# schematic.net
KiCad netlist of a schematic drawn in EAGLE
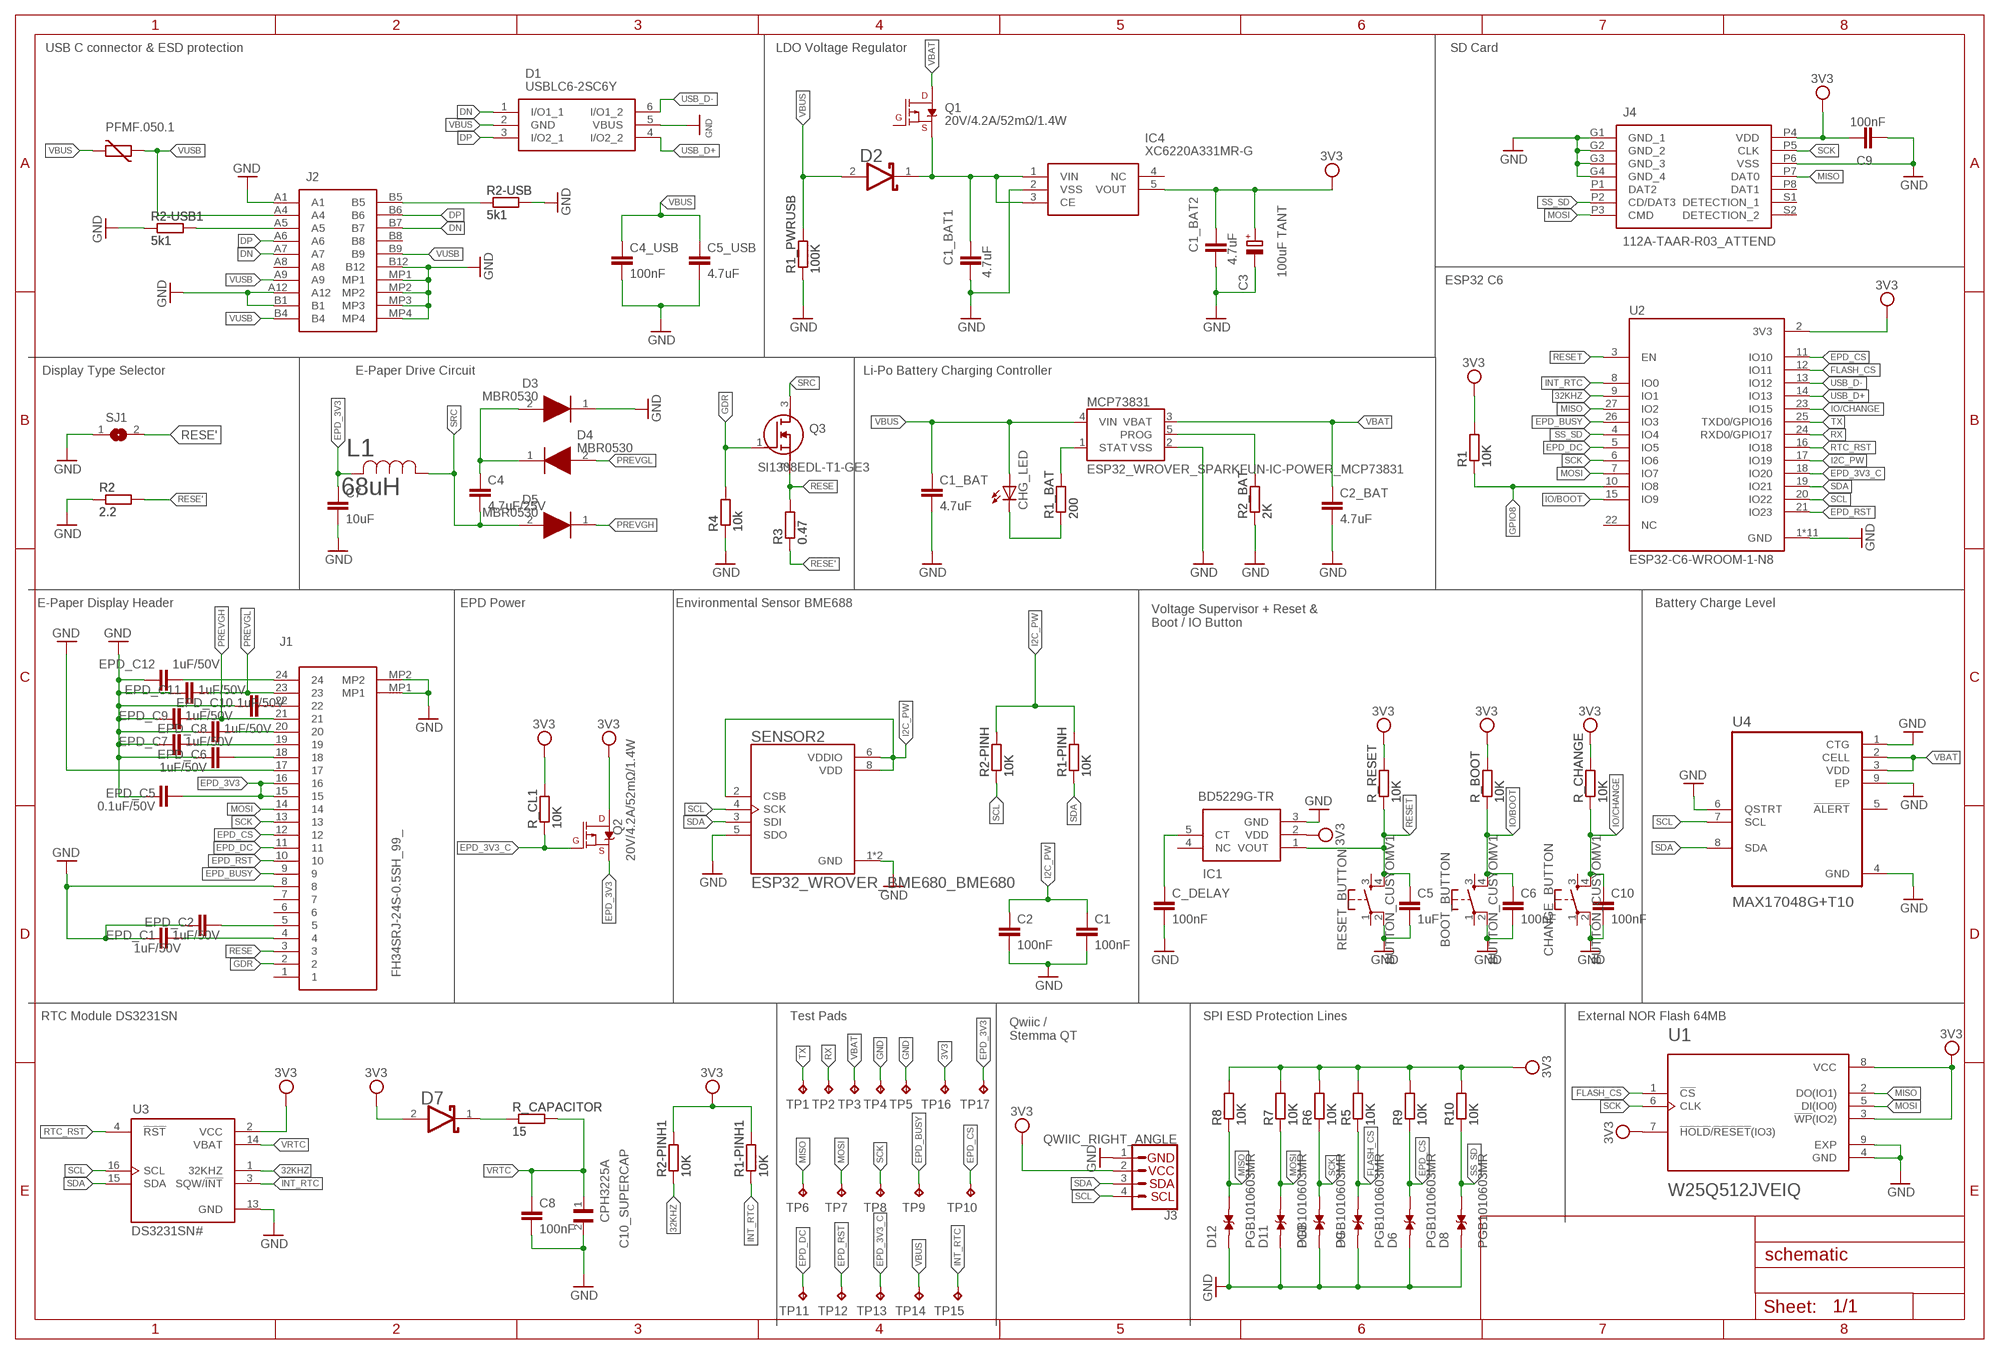
[diagram p0: schematic, sheet 1]

(export (version "E")
  (design (tool "Eeschema 10.0.6"))
  (components
    (comp (ref "BOOT_BUTTON")
      (value "BUTTON_CUSYOMV1")
      (footprint "eagle-import:MYBUTTON")
      (libsource (lib "eagle-import") (part "BUTTON_CUSYOMV1"))
    )
    (comp (ref "C1")
      (value "100nF")
      (footprint "eagle-import:EAGLE-LTSPICE_C0402")
      (libsource (lib "eagle-import") (part "ESP32_WROVER_EAGLE-LTSPICE_CC0402"))
    )
    (comp (ref "C1_BAT")
      (value "4.7uF")
      (footprint "eagle-import:EAGLE-LTSPICE_C0402")
      (libsource (lib "eagle-import") (part "ESP32_WROVER_EAGLE-LTSPICE_CC0402"))
    )
    (comp (ref "C1_BAT1")
      (value "4.7uF")
      (footprint "eagle-import:ESP32_WROVER_EAGLE-LTSPICE_C0402")
      (libsource (lib "eagle-import") (part "DeskAssistant v19 v1_vf.dFvje_iDQXiLOtX_eNBvag_EAGLE-LTSPICE_CC0402"))
    )
    (comp (ref "C1_BAT2")
      (value "4.7uF")
      (footprint "eagle-import:ESP32_WROVER_EAGLE-LTSPICE_C0402")
      (libsource (lib "eagle-import") (part "DeskAssistant v19 v1_vf.dFvje_iDQXiLOtX_eNBvag_EAGLE-LTSPICE_CC0402"))
    )
    (comp (ref "C2")
      (value "100nF")
      (footprint "eagle-import:EAGLE-LTSPICE_C0402")
      (libsource (lib "eagle-import") (part "ESP32_WROVER_EAGLE-LTSPICE_CC0402"))
    )
    (comp (ref "C2_BAT")
      (value "4.7uF")
      (footprint "eagle-import:EAGLE-LTSPICE_C0402")
      (libsource (lib "eagle-import") (part "ESP32_WROVER_EAGLE-LTSPICE_CC0402"))
    )
    (comp (ref "C3")
      (value "100uF TANT")
      (footprint "eagle-import:RCL_CT3528")
      (libsource (lib "eagle-import") (part "RCL_CPOL-EUCT3528"))
    )
    (comp (ref "C4")
      (value "4.7uF/25V")
      (footprint "eagle-import:EAGLE-LTSPICE_C0402")
      (libsource (lib "eagle-import") (part "ESP32_WROVER_EAGLE-LTSPICE_CC0402"))
    )
    (comp (ref "C4_USB")
      (value "100nF")
      (footprint "eagle-import:EAGLE-LTSPICE_C0402")
      (libsource (lib "eagle-import") (part "EAGLE-LTSPICE_CC0402"))
    )
    (comp (ref "C5")
      (value "1uF")
      (footprint "eagle-import:EAGLE-LTSPICE_C0402")
      (libsource (lib "eagle-import") (part "ESP32_WROVER_EAGLE-LTSPICE_CC0402"))
    )
    (comp (ref "C5_USB")
      (value "4.7uF")
      (footprint "eagle-import:EAGLE-LTSPICE_C0402")
      (libsource (lib "eagle-import") (part "EAGLE-LTSPICE_CC0402"))
    )
    (comp (ref "C6")
      (value "100nF")
      (footprint "eagle-import:EAGLE-LTSPICE_C0402")
      (libsource (lib "eagle-import") (part "ESP32_WROVER_EAGLE-LTSPICE_CC0402"))
    )
    (comp (ref "C7")
      (value "10uF")
      (footprint "eagle-import:EAGLE-LTSPICE_C0402")
      (libsource (lib "eagle-import") (part "ESP32_WROVER_EAGLE-LTSPICE_CC0402"))
    )
    (comp (ref "C8")
      (value "100nF")
      (footprint "eagle-import:EAGLE-LTSPICE_C0402")
      (libsource (lib "eagle-import") (part "ESP32_WROVER_EAGLE-LTSPICE_CC0402"))
    )
    (comp (ref "C9")
      (value "100nF")
      (footprint "eagle-import:ESP32_WROVER_EAGLE-LTSPICE_C0402")
      (libsource (lib "eagle-import") (part "DeskAssistant v19 v1_vf.dFvje_iDQXiLOtX_eNBvag_EAGLE-LTSPICE_CC0402"))
    )
    (comp (ref "C10")
      (value "100nF")
      (footprint "eagle-import:EAGLE-LTSPICE_C0402")
      (libsource (lib "eagle-import") (part "ESP32_WROVER_EAGLE-LTSPICE_CC0402"))
    )
    (comp (ref "C10_SUPERCAP")
      (value "CPH3225A")
      (footprint "eagle-import:CAPCP3225X100N")
      (fields (field (name "MF") "Seiko Instruments"))
      (libsource (lib "eagle-import") (part "CPH3225A"))
    )
    (comp (ref "CHANGE_BUTTON")
      (value "BUTTON_CUSYOMV1")
      (footprint "eagle-import:MYBUTTON")
      (libsource (lib "eagle-import") (part "BUTTON_CUSYOMV1"))
    )
    (comp (ref "CHG_LED")
      (value "ADAFRUIT_LEDCHIP-LED0603")
      (footprint "eagle-import:ADAFRUIT_CHIP-LED0603")
      (libsource (lib "eagle-import") (part "ADAFRUIT_LEDCHIP-LED0603"))
    )
    (comp (ref "C_DELAY")
      (value "100nF")
      (footprint "eagle-import:EAGLE-LTSPICE_C0402")
      (libsource (lib "eagle-import") (part "ESP32_WROVER_EAGLE-LTSPICE_CC0402"))
    )
    (comp (ref "D1")
      (value "USBLC6-2SC6Y")
      (footprint "eagle-import:SOT95P280X145-6N")
      (fields (field (name "MF") "STMicroelectronics"))
      (libsource (lib "eagle-import") (part "USBLC6-2SC6Y"))
    )
    (comp (ref "D2")
      (value "ESP32_WROVER_AVX---SD0805S020S1R0_AVX_SD0805S020S1R0_0_0AVX_SD0805S020S1R0_0_0")
      (footprint "eagle-import:ESP32_WROVER_AVX---SD0805S020S1R0_AVX_SD0805S020S1R0_0")
      (fields
        (field (name "DIGIKEY_PART_NUMBER") "478-7800-1-ND")
        (field (name "MF") "AVX")
        (field (name "MOUSER_PART_NUMBER") "581-SD0805S020S1R0")
      )
      (libsource (lib "eagle-import") (part "ESP32_WROVER_AVX---SD0805S020S1R0_AVX_SD0805S020S1R0_0_0AVX_SD0805S020S1R0_0_0"))
    )
    (comp (ref "D3")
      (value "MBR0530")
      (footprint "eagle-import:SOD3716X135N")
      (fields (field (name "MF") "ON Semiconductor"))
      (libsource (lib "eagle-import") (part "MBR0530"))
    )
    (comp (ref "D4")
      (value "MBR0530")
      (footprint "eagle-import:SOD3716X135N")
      (fields (field (name "MF") "ON Semiconductor"))
      (libsource (lib "eagle-import") (part "MBR0530"))
    )
    (comp (ref "D5")
      (value "MBR0530")
      (footprint "eagle-import:SOD3716X135N")
      (fields (field (name "MF") "ON Semiconductor"))
      (libsource (lib "eagle-import") (part "MBR0530"))
    )
    (comp (ref "D6")
      (value "PGB1010603MR")
      (footprint "eagle-import:DIOC1608X36N")
      (fields (field (name "MF") "Littelfuse Inc."))
      (libsource (lib "eagle-import") (part "PGB1010603MR"))
    )
    (comp (ref "D7")
      (value "ESP32_WROVER_AVX---SD0805S020S1R0_AVX_SD0805S020S1R0_0_0AVX_SD0805S020S1R0_0_0")
      (footprint "eagle-import:ESP32_WROVER_AVX---SD0805S020S1R0_AVX_SD0805S020S1R0_0")
      (fields
        (field (name "DIGIKEY_PART_NUMBER") "478-7800-1-ND")
        (field (name "MF") "AVX")
        (field (name "MOUSER_PART_NUMBER") "581-SD0805S020S1R0")
      )
      (libsource (lib "eagle-import") (part "ESP32_WROVER_AVX---SD0805S020S1R0_AVX_SD0805S020S1R0_0_0AVX_SD0805S020S1R0_0_0"))
    )
    (comp (ref "D8")
      (value "PGB1010603MR")
      (footprint "eagle-import:DIOC1608X36N")
      (fields (field (name "MF") "Littelfuse Inc."))
      (libsource (lib "eagle-import") (part "PGB1010603MR"))
    )
    (comp (ref "D9")
      (value "PGB1010603MR")
      (footprint "eagle-import:DIOC1608X36N")
      (fields (field (name "MF") "Littelfuse Inc."))
      (libsource (lib "eagle-import") (part "PGB1010603MR"))
    )
    (comp (ref "D10")
      (value "PGB1010603MR")
      (footprint "eagle-import:DIOC1608X36N")
      (fields (field (name "MF") "Littelfuse Inc."))
      (libsource (lib "eagle-import") (part "PGB1010603MR"))
    )
    (comp (ref "D11")
      (value "PGB1010603MR")
      (footprint "eagle-import:DIOC1608X36N")
      (fields (field (name "MF") "Littelfuse Inc."))
      (libsource (lib "eagle-import") (part "PGB1010603MR"))
    )
    (comp (ref "D12")
      (value "PGB1010603MR")
      (footprint "eagle-import:DIOC1608X36N")
      (fields (field (name "MF") "Littelfuse Inc."))
      (libsource (lib "eagle-import") (part "PGB1010603MR"))
    )
    (comp (ref "EPD_C1")
      (value "1uF/50V")
      (footprint "eagle-import:EAGLE-LTSPICE_C0402")
      (libsource (lib "eagle-import") (part "ESP32_WROVER_EAGLE-LTSPICE_CC0402"))
    )
    (comp (ref "EPD_C2")
      (value "1uF/50V")
      (footprint "eagle-import:EAGLE-LTSPICE_C0402")
      (libsource (lib "eagle-import") (part "ESP32_WROVER_EAGLE-LTSPICE_CC0402"))
    )
    (comp (ref "EPD_C5")
      (value "0.1uF/50V")
      (footprint "eagle-import:EAGLE-LTSPICE_C0402")
      (libsource (lib "eagle-import") (part "ESP32_WROVER_EAGLE-LTSPICE_CC0402"))
    )
    (comp (ref "EPD_C6")
      (value "1uF/50V")
      (footprint "eagle-import:EAGLE-LTSPICE_C0402")
      (libsource (lib "eagle-import") (part "ESP32_WROVER_EAGLE-LTSPICE_CC0402"))
    )
    (comp (ref "EPD_C7")
      (value "1uF/50V")
      (footprint "eagle-import:EAGLE-LTSPICE_C0402")
      (libsource (lib "eagle-import") (part "ESP32_WROVER_EAGLE-LTSPICE_CC0402"))
    )
    (comp (ref "EPD_C8")
      (value "1uF/50V")
      (footprint "eagle-import:EAGLE-LTSPICE_C0402")
      (libsource (lib "eagle-import") (part "ESP32_WROVER_EAGLE-LTSPICE_CC0402"))
    )
    (comp (ref "EPD_C9")
      (value "1uF/50V")
      (footprint "eagle-import:EAGLE-LTSPICE_C0402")
      (libsource (lib "eagle-import") (part "ESP32_WROVER_EAGLE-LTSPICE_CC0402"))
    )
    (comp (ref "EPD_C10")
      (value "1uF/50V")
      (footprint "eagle-import:EAGLE-LTSPICE_C0402")
      (libsource (lib "eagle-import") (part "ESP32_WROVER_EAGLE-LTSPICE_CC0402"))
    )
    (comp (ref "EPD_C11")
      (value "1uF/50V")
      (footprint "eagle-import:EAGLE-LTSPICE_C0402")
      (libsource (lib "eagle-import") (part "ESP32_WROVER_EAGLE-LTSPICE_CC0402"))
    )
    (comp (ref "EPD_C12")
      (value "1uF/50V")
      (footprint "eagle-import:EAGLE-LTSPICE_C0402")
      (libsource (lib "eagle-import") (part "ESP32_WROVER_EAGLE-LTSPICE_CC0402"))
    )
    (comp (ref "IC1")
      (value "BD5229G-TR")
      (footprint "eagle-import:SOT95P280X125-5N")
      (fields (field (name "MOUSER_PART_NUMBER") "755-BD5229G-TR"))
      (libsource (lib "eagle-import") (part "BD5229G-TR"))
    )
    (comp (ref "IC4")
      (value "XC6220A331MR-G")
      (footprint "eagle-import:SOT95P280X120-5N")
      (fields (field (name "MOUSER_PART_NUMBER") "865-XC6220A331MR-G"))
      (libsource (lib "eagle-import") (part "XC6220A331MR-G"))
    )
    (comp (ref "J1")
      (value "FH34SRJ-24S-0.5SH_99_")
      (footprint "eagle-import:FH34SRJ24S05SH99")
      (fields
        (field (name "MANUFACTURER_PART_NUMBER") "FH34SRJ-24S-0.5SH(99)")
        (field (name "MOUSER_PART_NUMBER") "798-FH34SRJ24S05SH99")
      )
      (libsource (lib "eagle-import") (part "FH34SRJ-24S-0.5SH_99_"))
    )
    (comp (ref "J2")
      (value "SAMACSYS_PARTS_USB4110-GF-A")
      (footprint "eagle-import:SAMACSYS_PARTS_USB4110GFA")
      (fields
        (field (name "MANUFACTURER_PART_NUMBER") "USB4110-GF-A")
        (field (name "MOUSER_PART_NUMBER") "640-USB4110-GF-A")
      )
      (libsource (lib "eagle-import") (part "SAMACSYS_PARTS_USB4110-GF-A"))
    )
    (comp (ref "J3")
      (value "QWIIC_RIGHT_ANGLE")
      (footprint "eagle-import:JST04_1MM_RA")
      (libsource (lib "eagle-import") (part "QWIIC_CONNECTORJS-1MM"))
    )
    (comp (ref "J4")
      (value "112A-TAAR-R03_ATTEND")
      (footprint "eagle-import:112ATAARR03ATTEND")
      (fields (field (name "MANUFACTURER_PART_NUMBER") "112A-TAAR-R03 ATTEND"))
      (libsource (lib "eagle-import") (part "112A-TAAR-R03_ATTEND"))
    )
    (comp (ref "L1")
      (value "68uH")
      (footprint "eagle-import:IND_4828-WE-TPC_WRE")
      (fields
        (field (name "MANUFACTURER_PART_NUMBER") "744043680")
        (field (name "COPYRIGHT") "Copyright (C) 2024 Ultra Librarian. All rights reserved.")
      )
      (libsource (lib "eagle-import") (part "744043680IND_4828-WE-TPC_WRE"))
    )
    (comp (ref "MCP73831")
      (value "ESP32_WROVER_SPARKFUN-IC-POWER_MCP73831")
      (footprint "eagle-import:ESP32_WROVER_SPARKFUN-IC-POWER_SOT23-5")
      (libsource (lib "eagle-import") (part "ESP32_WROVER_SPARKFUN-IC-POWER_MCP73831"))
    )
    (comp (ref "PFMF.050.1")
      (value "ESP32C6_VARISTORCN1812")
      (footprint "eagle-import:ESP32C6_VARISTOR_CT_CN1812")
      (libsource (lib "eagle-import") (part "ESP32C6_VARISTORCN1812"))
    )
    (comp (ref "Q1")
      (value "20V/4.2A/52mΩ/1.4W")
      (footprint "eagle-import:ESP32_WROVER_SPARKFUN-DISCRETESEMI_SOT23-3")
      (libsource (lib "eagle-import") (part "ESP32_WROVER_SPARKFUN-DISCRETESEMI_MOSFET_PCH-DMG2305UX-7"))
    )
    (comp (ref "Q2")
      (value "20V/4.2A/52mΩ/1.4W")
      (footprint "eagle-import:ESP32_WROVER_SPARKFUN-DISCRETESEMI_SOT23-3")
      (libsource (lib "eagle-import") (part "ESP32_WROVER_SPARKFUN-DISCRETESEMI_MOSFET_PCH-DMG2305UX-7"))
    )
    (comp (ref "Q3")
      (value "SI1308EDL-T1-GE3")
      (footprint "eagle-import:SOT65P210X110-3N")
      (fields (field (name "MF") "Vishay Siliconix"))
      (libsource (lib "eagle-import") (part "SI1308EDL-T1-GE3"))
    )
    (comp (ref "R1")
      (value "10K")
      (footprint "eagle-import:ESP32_WROVER_EAGLE-LTSPICE_R0402")
      (libsource (lib "eagle-import") (part "DeskAssistant v19 v1_vf.dFvje_iDQXiLOtX_eNBvag_ESP32_WROVER_EAGLE-LTSPICE_RR0402"))
    )
    (comp (ref "R1-PINH")
      (value "10K")
      (footprint "eagle-import:ESP32_WROVER_EAGLE-LTSPICE_R0402")
      (libsource (lib "eagle-import") (part "DeskAssistant v19 v1_vf.dFvje_iDQXiLOtX_eNBvag_ESP32_WROVER_EAGLE-LTSPICE_RR0402"))
    )
    (comp (ref "R1-PINH1")
      (value "10K")
      (footprint "eagle-import:ESP32_WROVER_EAGLE-LTSPICE_R0402")
      (libsource (lib "eagle-import") (part "DeskAssistant v19 v1_vf.dFvje_iDQXiLOtX_eNBvag_ESP32_WROVER_EAGLE-LTSPICE_RR0402"))
    )
    (comp (ref "R1_BAT")
      (value "200")
      (footprint "eagle-import:ESP32_WROVER_EAGLE-LTSPICE_R0402")
      (libsource (lib "eagle-import") (part "DeskAssistant v19 v1_vf.dFvje_iDQXiLOtX_eNBvag_ESP32_WROVER_EAGLE-LTSPICE_RR0402"))
    )
    (comp (ref "R1_PWRUSB")
      (value "100K")
      (footprint "eagle-import:ESP32_WROVER_EAGLE-LTSPICE_R0402")
      (libsource (lib "eagle-import") (part "DeskAssistant v19 v1_vf.dFvje_iDQXiLOtX_eNBvag_ESP32_WROVER_EAGLE-LTSPICE_RR0402"))
    )
    (comp (ref "R2")
      (value "2.2")
      (footprint "eagle-import:ESP32_WROVER_EAGLE-LTSPICE_R0402")
      (libsource (lib "eagle-import") (part "DeskAssistant v19 v1_vf.dFvje_iDQXiLOtX_eNBvag_ESP32_WROVER_EAGLE-LTSPICE_RR0402"))
    )
    (comp (ref "R2-PINH")
      (value "10K")
      (footprint "eagle-import:ESP32_WROVER_EAGLE-LTSPICE_R0402")
      (libsource (lib "eagle-import") (part "DeskAssistant v19 v1_vf.dFvje_iDQXiLOtX_eNBvag_ESP32_WROVER_EAGLE-LTSPICE_RR0402"))
    )
    (comp (ref "R2-PINH1")
      (value "10K")
      (footprint "eagle-import:ESP32_WROVER_EAGLE-LTSPICE_R0402")
      (libsource (lib "eagle-import") (part "DeskAssistant v19 v1_vf.dFvje_iDQXiLOtX_eNBvag_ESP32_WROVER_EAGLE-LTSPICE_RR0402"))
    )
    (comp (ref "R2-USB")
      (value "5k1")
      (footprint "eagle-import:ESP32_WROVER_EAGLE-LTSPICE_R0402")
      (libsource (lib "eagle-import") (part "ESP32_WROVER_EAGLE-LTSPICE_RR0402"))
    )
    (comp (ref "R2-USB1")
      (value "5k1")
      (footprint "eagle-import:ESP32_WROVER_EAGLE-LTSPICE_R0402")
      (libsource (lib "eagle-import") (part "ESP32_WROVER_EAGLE-LTSPICE_RR0402"))
    )
    (comp (ref "R2_BAT")
      (value "2K")
      (footprint "eagle-import:ESP32_WROVER_EAGLE-LTSPICE_R0402")
      (libsource (lib "eagle-import") (part "DeskAssistant v19 v1_vf.dFvje_iDQXiLOtX_eNBvag_ESP32_WROVER_EAGLE-LTSPICE_RR0402"))
    )
    (comp (ref "R3")
      (value "0.47")
      (footprint "eagle-import:ESP32_WROVER_EAGLE-LTSPICE_R0402")
      (libsource (lib "eagle-import") (part "DeskAssistant v19 v1_vf.dFvje_iDQXiLOtX_eNBvag_ESP32_WROVER_EAGLE-LTSPICE_RR0402"))
    )
    (comp (ref "R4")
      (value "10k")
      (footprint "eagle-import:ESP32_WROVER_EAGLE-LTSPICE_R0402")
      (libsource (lib "eagle-import") (part "DeskAssistant v19 v1_vf.dFvje_iDQXiLOtX_eNBvag_ESP32_WROVER_EAGLE-LTSPICE_RR0402"))
    )
    (comp (ref "R5")
      (value "10K")
      (footprint "eagle-import:ESP32_WROVER_EAGLE-LTSPICE_R0402")
      (libsource (lib "eagle-import") (part "DeskAssistant v19 v1_vf.dFvje_iDQXiLOtX_eNBvag_ESP32_WROVER_EAGLE-LTSPICE_RR0402"))
    )
    (comp (ref "R6")
      (value "10K")
      (footprint "eagle-import:ESP32_WROVER_EAGLE-LTSPICE_R0402")
      (libsource (lib "eagle-import") (part "DeskAssistant v19 v1_vf.dFvje_iDQXiLOtX_eNBvag_ESP32_WROVER_EAGLE-LTSPICE_RR0402"))
    )
    (comp (ref "R7")
      (value "10K")
      (footprint "eagle-import:ESP32_WROVER_EAGLE-LTSPICE_R0402")
      (libsource (lib "eagle-import") (part "DeskAssistant v19 v1_vf.dFvje_iDQXiLOtX_eNBvag_ESP32_WROVER_EAGLE-LTSPICE_RR0402"))
    )
    (comp (ref "R8")
      (value "10K")
      (footprint "eagle-import:ESP32_WROVER_EAGLE-LTSPICE_R0402")
      (libsource (lib "eagle-import") (part "DeskAssistant v19 v1_vf.dFvje_iDQXiLOtX_eNBvag_ESP32_WROVER_EAGLE-LTSPICE_RR0402"))
    )
    (comp (ref "R9")
      (value "10K")
      (footprint "eagle-import:ESP32_WROVER_EAGLE-LTSPICE_R0402")
      (libsource (lib "eagle-import") (part "DeskAssistant v19 v1_vf.dFvje_iDQXiLOtX_eNBvag_ESP32_WROVER_EAGLE-LTSPICE_RR0402"))
    )
    (comp (ref "R10")
      (value "10K")
      (footprint "eagle-import:ESP32_WROVER_EAGLE-LTSPICE_R0402")
      (libsource (lib "eagle-import") (part "DeskAssistant v19 v1_vf.dFvje_iDQXiLOtX_eNBvag_ESP32_WROVER_EAGLE-LTSPICE_RR0402"))
    )
    (comp (ref "RESET_BUTTON")
      (value "BUTTON_CUSYOMV1")
      (footprint "eagle-import:MYBUTTON")
      (libsource (lib "eagle-import") (part "BUTTON_CUSYOMV1"))
    )
    (comp (ref "R_BOOT")
      (value "10K")
      (footprint "eagle-import:ESP32_WROVER_EAGLE-LTSPICE_R0402")
      (libsource (lib "eagle-import") (part "DeskAssistant v19 v1_vf.dFvje_iDQXiLOtX_eNBvag_ESP32_WROVER_EAGLE-LTSPICE_RR0402"))
    )
    (comp (ref "R_CAPACITOR")
      (value "15")
      (footprint "eagle-import:ESP32_WROVER_EAGLE-LTSPICE_R0402")
      (libsource (lib "eagle-import") (part "DeskAssistant v19 v1_vf.dFvje_iDQXiLOtX_eNBvag_ESP32_WROVER_EAGLE-LTSPICE_RR0402"))
    )
    (comp (ref "R_CHANGE")
      (value "10K")
      (footprint "eagle-import:ESP32_WROVER_EAGLE-LTSPICE_R0402")
      (libsource (lib "eagle-import") (part "DeskAssistant v19 v1_vf.dFvje_iDQXiLOtX_eNBvag_ESP32_WROVER_EAGLE-LTSPICE_RR0402"))
    )
    (comp (ref "R_CL1")
      (value "10K")
      (footprint "eagle-import:ESP32_WROVER_EAGLE-LTSPICE_R0402")
      (libsource (lib "eagle-import") (part "DeskAssistant v19 v1_vf.dFvje_iDQXiLOtX_eNBvag_ESP32_WROVER_EAGLE-LTSPICE_RR0402"))
    )
    (comp (ref "R_RESET")
      (value "10K")
      (footprint "eagle-import:ESP32_WROVER_EAGLE-LTSPICE_R0402")
      (libsource (lib "eagle-import") (part "DeskAssistant v19 v1_vf.dFvje_iDQXiLOtX_eNBvag_ESP32_WROVER_EAGLE-LTSPICE_RR0402"))
    )
    (comp (ref "SENSOR2")
      (value "ESP32_WROVER_BME680_BME680")
      (footprint "eagle-import:ESP32_WROVER_BME680_PSON80P300X300X100-8N")
      (fields (field (name "MF") "Bosch Sensortec") (field (name "MP") "BME680"))
      (libsource (lib "eagle-import") (part "ESP32_WROVER_BME680_BME680"))
    )
    (comp (ref "SJ1") (value "SJ") (footprint "eagle-import:SJ") (libsource (lib "eagle-import") (part "SJ")))
    (comp (ref "TP1")
      (value "TPTP20R")
      (footprint "eagle-import:TP20R")
      (libsource (lib "eagle-import") (part "TPTP20R"))
    )
    (comp (ref "TP2")
      (value "TPTP20R")
      (footprint "eagle-import:TP20R")
      (libsource (lib "eagle-import") (part "TPTP20R"))
    )
    (comp (ref "TP3")
      (value "TPTP20R")
      (footprint "eagle-import:TP20R")
      (libsource (lib "eagle-import") (part "TPTP20R"))
    )
    (comp (ref "TP4")
      (value "TPTP20R")
      (footprint "eagle-import:TP20R")
      (libsource (lib "eagle-import") (part "TPTP20R"))
    )
    (comp (ref "TP5")
      (value "TPTP20R")
      (footprint "eagle-import:TP20R")
      (libsource (lib "eagle-import") (part "TPTP20R"))
    )
    (comp (ref "TP6")
      (value "TPTP20R")
      (footprint "eagle-import:TP20R")
      (libsource (lib "eagle-import") (part "TPTP20R"))
    )
    (comp (ref "TP7")
      (value "TPTP20R")
      (footprint "eagle-import:TP20R")
      (libsource (lib "eagle-import") (part "TPTP20R"))
    )
    (comp (ref "TP8")
      (value "TPTP20R")
      (footprint "eagle-import:TP20R")
      (libsource (lib "eagle-import") (part "TPTP20R"))
    )
    (comp (ref "TP9")
      (value "TPTP20R")
      (footprint "eagle-import:TP20R")
      (libsource (lib "eagle-import") (part "TPTP20R"))
    )
    (comp (ref "TP10")
      (value "TPTP20R")
      (footprint "eagle-import:TP20R")
      (libsource (lib "eagle-import") (part "TPTP20R"))
    )
    (comp (ref "TP11")
      (value "TPTP20R")
      (footprint "eagle-import:TP20R")
      (libsource (lib "eagle-import") (part "TPTP20R"))
    )
    (comp (ref "TP12")
      (value "TPTP20R")
      (footprint "eagle-import:TP20R")
      (libsource (lib "eagle-import") (part "TPTP20R"))
    )
    (comp (ref "TP13")
      (value "TPTP20R")
      (footprint "eagle-import:TP20R")
      (libsource (lib "eagle-import") (part "TPTP20R"))
    )
    (comp (ref "TP14")
      (value "TPTP20R")
      (footprint "eagle-import:TP20R")
      (libsource (lib "eagle-import") (part "TPTP20R"))
    )
    (comp (ref "TP15")
      (value "TPTP20R")
      (footprint "eagle-import:TP20R")
      (libsource (lib "eagle-import") (part "TPTP20R"))
    )
    (comp (ref "TP16")
      (value "TPTP20R")
      (footprint "eagle-import:TP20R")
      (libsource (lib "eagle-import") (part "TPTP20R"))
    )
    (comp (ref "TP17")
      (value "TPTP20R")
      (footprint "eagle-import:TP20R")
      (libsource (lib "eagle-import") (part "TPTP20R"))
    )
    (comp (ref "U1")
      (value "W25Q512JVEIQ")
      (footprint "eagle-import:SON127P600X800X80-9N")
      (fields (field (name "MF") "Winbond Electronics"))
      (libsource (lib "eagle-import") (part "W25Q512JVEIQ"))
    )
    (comp (ref "U2")
      (value "ESP32-C6-WROOM-1-N8")
      (footprint "eagle-import:XCVR_ESP32-C6-WROOM-1-N8")
      (fields (field (name "MF") "Espressif Systems"))
      (libsource (lib "eagle-import") (part "ESP32-C6-WROOM-1-N8"))
    )
    (comp (ref "U3")
      (value "DS3231SN#")
      (footprint "eagle-import:SOIC127P1032X265-16N")
      (fields (field (name "MF") "Analog Devices"))
      (libsource (lib "eagle-import") (part "DS3231SN#"))
    )
    (comp (ref "U4")
      (value "MAX17048G+T10")
      (footprint "eagle-import:SON50P200X200X80-9N")
      (fields (field (name "MF") "Analog Devices"))
      (libsource (lib "eagle-import") (part "MAX17048G+T10"))
    )
  )
  (nets
    (net (code "1") (name "3V3") (class "Default")
      (node (ref "C1_BAT2") (pin "1") (pinfunction "1_1") (pintype "passive"))
      (node (ref "C3") (pin "+") (pinfunction "+_+") (pintype "passive"))
      (node (ref "C9") (pin "1") (pinfunction "1_1") (pintype "passive"))
      (node (ref "D7") (pin "2") (pinfunction "ANODE_2") (pintype "bidirectional"))
      (node (ref "IC1") (pin "2") (pinfunction "VDD_2") (pintype "bidirectional"))
      (node (ref "IC4") (pin "5") (pinfunction "VOUT_5") (pintype "bidirectional"))
      (node (ref "J3") (pin "2") (pinfunction "2_2") (pintype "power_in"))
      (node (ref "J4") (pin "P4") (pinfunction "VDD_P4") (pintype "bidirectional"))
      (node (ref "Q2") (pin "3") (pinfunction "D_3") (pintype "bidirectional"))
      (node (ref "R1") (pin "2") (pinfunction "2_2") (pintype "passive"))
      (node (ref "R1-PINH1") (pin "2") (pinfunction "2_2") (pintype "passive"))
      (node (ref "R10") (pin "2") (pinfunction "2_2") (pintype "passive"))
      (node (ref "R2-PINH1") (pin "2") (pinfunction "2_2") (pintype "passive"))
      (node (ref "R5") (pin "2") (pinfunction "2_2") (pintype "passive"))
      (node (ref "R6") (pin "2") (pinfunction "2_2") (pintype "passive"))
      (node (ref "R7") (pin "2") (pinfunction "2_2") (pintype "passive"))
      (node (ref "R8") (pin "2") (pinfunction "2_2") (pintype "passive"))
      (node (ref "R9") (pin "2") (pinfunction "2_2") (pintype "passive"))
      (node (ref "R_BOOT") (pin "2") (pinfunction "2_2") (pintype "passive"))
      (node (ref "R_CHANGE") (pin "2") (pinfunction "2_2") (pintype "passive"))
      (node (ref "R_CL1") (pin "2") (pinfunction "2_2") (pintype "passive"))
      (node (ref "R_RESET") (pin "2") (pinfunction "2_2") (pintype "passive"))
      (node (ref "TP16") (pin "TP") (pinfunction "TP_TP") (pintype "input"))
      (node (ref "U1") (pin "3") (pinfunction "~{WP}(IO2)_3") (pintype "bidirectional"))
      (node (ref "U1") (pin "7") (pinfunction "~{HOLD}/~{RESET}(IO3)_7") (pintype "bidirectional"))
      (node (ref "U1") (pin "8") (pinfunction "VCC_8") (pintype "power_in"))
      (node (ref "U2") (pin "2") (pinfunction "3V3_2") (pintype "power_in"))
      (node (ref "U3") (pin "2") (pinfunction "VCC_2") (pintype "power_in"))
    )
    (net (code "2") (name "32KHZ") (class "Default")
      (node (ref "R2-PINH1") (pin "1") (pinfunction "1_1") (pintype "passive"))
      (node (ref "U2") (pin "9") (pinfunction "IO1_9") (pintype "bidirectional"))
      (node (ref "U3") (pin "1") (pinfunction "32KHZ_1") (pintype "output"))
    )
    (net (code "3") (name "DN") (class "Default")
      (node (ref "D1") (pin "1") (pinfunction "I/O1_1_1") (pintype "bidirectional"))
      (node (ref "J2") (pin "A7") (pinfunction "A7_A7") (pintype "bidirectional"))
      (node (ref "J2") (pin "B7") (pinfunction "B7_B7") (pintype "bidirectional"))
    )
    (net (code "4") (name "DP") (class "Default")
      (node (ref "D1") (pin "3") (pinfunction "I/O2_1_3") (pintype "bidirectional"))
      (node (ref "J2") (pin "A6") (pinfunction "A6_A6") (pintype "bidirectional"))
      (node (ref "J2") (pin "B6") (pinfunction "B6_B6") (pintype "bidirectional"))
    )
    (net (code "5") (name "EPD_3V3") (class "Default")
      (node (ref "C7") (pin "1") (pinfunction "1_1") (pintype "passive"))
      (node (ref "EPD_C5") (pin "2") (pinfunction "2_2") (pintype "passive"))
      (node (ref "J1") (pin "15") (pinfunction "15_15") (pintype "bidirectional"))
      (node (ref "J1") (pin "16") (pinfunction "16_16") (pintype "bidirectional"))
      (node (ref "L1") (pin "2") (pinfunction "2_2") (pintype "passive"))
      (node (ref "Q2") (pin "2") (pinfunction "S_2") (pintype "bidirectional"))
      (node (ref "TP17") (pin "TP") (pinfunction "TP_TP") (pintype "input"))
    )
    (net (code "6") (name "EPD_3V3_C") (class "Default")
      (node (ref "Q2") (pin "1") (pinfunction "G_1") (pintype "bidirectional"))
      (node (ref "R_CL1") (pin "1") (pinfunction "1_1") (pintype "passive"))
      (node (ref "TP13") (pin "TP") (pinfunction "TP_TP") (pintype "input"))
      (node (ref "U2") (pin "18") (pinfunction "IO20_18") (pintype "bidirectional"))
    )
    (net (code "7") (name "EPD_BUSY") (class "Default")
      (node (ref "J1") (pin "9") (pinfunction "9_9") (pintype "bidirectional"))
      (node (ref "TP9") (pin "TP") (pinfunction "TP_TP") (pintype "input"))
      (node (ref "U2") (pin "26") (pinfunction "IO3_26") (pintype "bidirectional"))
    )
    (net (code "8") (name "EPD_CS") (class "Default")
      (node (ref "D6") (pin "2") (pinfunction "2_2") (pintype "passive"))
      (node (ref "J1") (pin "12") (pinfunction "12_12") (pintype "bidirectional"))
      (node (ref "R9") (pin "1") (pinfunction "1_1") (pintype "passive"))
      (node (ref "TP10") (pin "TP") (pinfunction "TP_TP") (pintype "input"))
      (node (ref "U2") (pin "11") (pinfunction "IO10_11") (pintype "bidirectional"))
    )
    (net (code "9") (name "EPD_DC") (class "Default")
      (node (ref "J1") (pin "11") (pinfunction "11_11") (pintype "bidirectional"))
      (node (ref "TP11") (pin "TP") (pinfunction "TP_TP") (pintype "input"))
      (node (ref "U2") (pin "5") (pinfunction "IO5_5") (pintype "bidirectional"))
    )
    (net (code "10") (name "EPD_RST") (class "Default")
      (node (ref "J1") (pin "10") (pinfunction "10_10") (pintype "bidirectional"))
      (node (ref "TP12") (pin "TP") (pinfunction "TP_TP") (pintype "input"))
      (node (ref "U2") (pin "21") (pinfunction "IO23_21") (pintype "bidirectional"))
    )
    (net (code "11") (name "FLASH_CS") (class "Default")
      (node (ref "D9") (pin "2") (pinfunction "2_2") (pintype "passive"))
      (node (ref "R5") (pin "1") (pinfunction "1_1") (pintype "passive"))
      (node (ref "U1") (pin "1") (pinfunction "~{CS}_1") (pintype "input"))
      (node (ref "U2") (pin "12") (pinfunction "IO11_12") (pintype "bidirectional"))
    )
    (net (code "12") (name "GDR") (class "Default")
      (node (ref "J1") (pin "2") (pinfunction "2_2") (pintype "bidirectional"))
      (node (ref "Q3") (pin "1") (pinfunction "G_1") (pintype "bidirectional"))
      (node (ref "R4") (pin "2") (pinfunction "2_2") (pintype "passive"))
    )
    (net (code "13") (name "GND") (class "Default")
      (node (ref "BOOT_BUTTON") (pin "2") (pinfunction "2_2") (pintype "passive"))
      (node (ref "C1") (pin "2") (pinfunction "2_2") (pintype "passive"))
      (node (ref "C10") (pin "2") (pinfunction "2_2") (pintype "passive"))
      (node (ref "C10_SUPERCAP") (pin "2") (pinfunction "2_2") (pintype "passive"))
      (node (ref "C1_BAT") (pin "2") (pinfunction "2_2") (pintype "passive"))
      (node (ref "C1_BAT1") (pin "2") (pinfunction "2_2") (pintype "passive"))
      (node (ref "C1_BAT2") (pin "2") (pinfunction "2_2") (pintype "passive"))
      (node (ref "C2") (pin "2") (pinfunction "2_2") (pintype "passive"))
      (node (ref "C2_BAT") (pin "2") (pinfunction "2_2") (pintype "passive"))
      (node (ref "C3") (pin "-") (pinfunction "-_-") (pintype "passive"))
      (node (ref "C4_USB") (pin "2") (pinfunction "2_2") (pintype "passive"))
      (node (ref "C5") (pin "2") (pinfunction "2_2") (pintype "passive"))
      (node (ref "C5_USB") (pin "2") (pinfunction "2_2") (pintype "passive"))
      (node (ref "C6") (pin "2") (pinfunction "2_2") (pintype "passive"))
      (node (ref "C7") (pin "2") (pinfunction "2_2") (pintype "passive"))
      (node (ref "C8") (pin "2") (pinfunction "2_2") (pintype "passive"))
      (node (ref "C9") (pin "2") (pinfunction "2_2") (pintype "passive"))
      (node (ref "CHANGE_BUTTON") (pin "2") (pinfunction "2_2") (pintype "passive"))
      (node (ref "C_DELAY") (pin "2") (pinfunction "2_2") (pintype "passive"))
      (node (ref "D1") (pin "5") (pinfunction "VBUS_5") (pintype "bidirectional"))
      (node (ref "D10") (pin "1") (pinfunction "1_1") (pintype "passive"))
      (node (ref "D11") (pin "1") (pinfunction "1_1") (pintype "passive"))
      (node (ref "D12") (pin "1") (pinfunction "1_1") (pintype "passive"))
      (node (ref "D3") (pin "1") (pinfunction "K_1") (pintype "bidirectional"))
      (node (ref "D6") (pin "1") (pinfunction "1_1") (pintype "passive"))
      (node (ref "D8") (pin "1") (pinfunction "1_1") (pintype "passive"))
      (node (ref "D9") (pin "1") (pinfunction "1_1") (pintype "passive"))
      (node (ref "EPD_C1") (pin "1") (pinfunction "1_1") (pintype "passive"))
      (node (ref "EPD_C10") (pin "1") (pinfunction "1_1") (pintype "passive"))
      (node (ref "EPD_C11") (pin "1") (pinfunction "1_1") (pintype "passive"))
      (node (ref "EPD_C12") (pin "1") (pinfunction "1_1") (pintype "passive"))
      (node (ref "EPD_C2") (pin "1") (pinfunction "1_1") (pintype "passive"))
      (node (ref "EPD_C5") (pin "1") (pinfunction "1_1") (pintype "passive"))
      (node (ref "EPD_C6") (pin "1") (pinfunction "1_1") (pintype "passive"))
      (node (ref "EPD_C7") (pin "1") (pinfunction "1_1") (pintype "passive"))
      (node (ref "EPD_C8") (pin "1") (pinfunction "1_1") (pintype "passive"))
      (node (ref "EPD_C9") (pin "1") (pinfunction "1_1") (pintype "passive"))
      (node (ref "IC1") (pin "3") (pinfunction "GND_3") (pintype "bidirectional"))
      (node (ref "IC4") (pin "2") (pinfunction "VSS_2") (pintype "bidirectional"))
      (node (ref "J1") (pin "17") (pinfunction "17_17") (pintype "bidirectional"))
      (node (ref "J1") (pin "8") (pinfunction "8_8") (pintype "bidirectional"))
      (node (ref "J1") (pin "MP1") (pinfunction "MP1_MP1") (pintype "bidirectional"))
      (node (ref "J1") (pin "MP2") (pinfunction "MP2_MP2") (pintype "bidirectional"))
      (node (ref "J2") (pin "A1") (pinfunction "A1_A1") (pintype "bidirectional"))
      (node (ref "J2") (pin "A12") (pinfunction "A12_A12") (pintype "bidirectional"))
      (node (ref "J2") (pin "B1") (pinfunction "B1_B1") (pintype "bidirectional"))
      (node (ref "J2") (pin "B12") (pinfunction "B12_B12") (pintype "bidirectional"))
      (node (ref "J2") (pin "MP1") (pinfunction "MP1_MP1") (pintype "bidirectional"))
      (node (ref "J2") (pin "MP2") (pinfunction "MP2_MP2") (pintype "bidirectional"))
      (node (ref "J2") (pin "MP3") (pinfunction "MP3_MP3") (pintype "bidirectional"))
      (node (ref "J2") (pin "MP4") (pinfunction "MP4_MP4") (pintype "bidirectional"))
      (node (ref "J3") (pin "1") (pinfunction "1_1") (pintype "power_in"))
      (node (ref "J4") (pin "G1") (pinfunction "GND_1_G1") (pintype "bidirectional"))
      (node (ref "J4") (pin "G2") (pinfunction "GND_2_G2") (pintype "bidirectional"))
      (node (ref "J4") (pin "G3") (pinfunction "GND_3_G3") (pintype "bidirectional"))
      (node (ref "J4") (pin "G4") (pinfunction "GND_4_G4") (pintype "bidirectional"))
      (node (ref "J4") (pin "P6") (pinfunction "VSS_P6") (pintype "bidirectional"))
      (node (ref "MCP73831") (pin "2") (pinfunction "VSS_2") (pintype "power_in"))
      (node (ref "R1_PWRUSB") (pin "1") (pinfunction "1_1") (pintype "passive"))
      (node (ref "R2") (pin "1") (pinfunction "1_1") (pintype "passive"))
      (node (ref "R2-USB") (pin "2") (pinfunction "2_2") (pintype "passive"))
      (node (ref "R2-USB1") (pin "1") (pinfunction "1_1") (pintype "passive"))
      (node (ref "R2_BAT") (pin "1") (pinfunction "1_1") (pintype "passive"))
      (node (ref "R4") (pin "1") (pinfunction "1_1") (pintype "passive"))
      (node (ref "RESET_BUTTON") (pin "2") (pinfunction "2_2") (pintype "passive"))
      (node (ref "SENSOR2") (pin "1") (pinfunction "GND_1") (pintype "power_in"))
      (node (ref "SENSOR2") (pin "5") (pinfunction "SDO_5") (pintype "bidirectional"))
      (node (ref "SENSOR2") (pin "7") (pinfunction "GND_7") (pintype "power_in"))
      (node (ref "SJ1") (pin "1") (pinfunction "1_1") (pintype "passive"))
      (node (ref "TP4") (pin "TP") (pinfunction "TP_TP") (pintype "input"))
      (node (ref "TP5") (pin "TP") (pinfunction "TP_TP") (pintype "input"))
      (node (ref "U1") (pin "4") (pinfunction "GND_4") (pintype "power_in"))
      (node (ref "U1") (pin "9") (pinfunction "EXP_9") (pintype "passive"))
      (node (ref "U2") (pin "1") (pinfunction "GND_1") (pintype "power_in"))
      (node (ref "U2") (pin "28") (pinfunction "GND_28") (pintype "power_in"))
      (node (ref "U2") (pin "29_1") (pinfunction "GND_29_1") (pintype "power_in"))
      (node (ref "U2") (pin "29_2") (pinfunction "GND_29_2") (pintype "power_in"))
      (node (ref "U2") (pin "29_3") (pinfunction "GND_29_3") (pintype "power_in"))
      (node (ref "U2") (pin "29_4") (pinfunction "GND_29_4") (pintype "power_in"))
      (node (ref "U2") (pin "29_5") (pinfunction "GND_29_5") (pintype "power_in"))
      (node (ref "U2") (pin "29_6") (pinfunction "GND_29_6") (pintype "power_in"))
      (node (ref "U2") (pin "29_7") (pinfunction "GND_29_7") (pintype "power_in"))
      (node (ref "U2") (pin "29_8") (pinfunction "GND_29_8") (pintype "power_in"))
      (node (ref "U2") (pin "29_9") (pinfunction "GND_29_9") (pintype "power_in"))
      (node (ref "U3") (pin "13") (pinfunction "GND_13") (pintype "power_in"))
      (node (ref "U4") (pin "1") (pinfunction "CTG_1") (pintype "power_in"))
      (node (ref "U4") (pin "4") (pinfunction "GND_4") (pintype "power_in"))
      (node (ref "U4") (pin "6") (pinfunction "QSTRT_6") (pintype "input"))
      (node (ref "U4") (pin "9") (pinfunction "EP_9") (pintype "power_in"))
    )
    (net (code "14") (name "GPIO8") (class "Default")
      (node (ref "R1") (pin "1") (pinfunction "1_1") (pintype "passive"))
      (node (ref "U2") (pin "10") (pinfunction "IO8_10") (pintype "bidirectional"))
    )
    (net (code "15") (name "I2C_PW") (class "Default")
      (node (ref "C1") (pin "1") (pinfunction "1_1") (pintype "passive"))
      (node (ref "C2") (pin "1") (pinfunction "1_1") (pintype "passive"))
      (node (ref "R1-PINH") (pin "2") (pinfunction "2_2") (pintype "passive"))
      (node (ref "R2-PINH") (pin "2") (pinfunction "2_2") (pintype "passive"))
      (node (ref "SENSOR2") (pin "2") (pinfunction "CSB_2") (pintype "input"))
      (node (ref "SENSOR2") (pin "6") (pinfunction "VDDIO_6") (pintype "power_in"))
      (node (ref "SENSOR2") (pin "8") (pinfunction "VDD_8") (pintype "power_in"))
      (node (ref "U2") (pin "17") (pinfunction "IO19_17") (pintype "bidirectional"))
    )
    (net (code "16") (name "INT_RTC") (class "Default")
      (node (ref "R1-PINH1") (pin "1") (pinfunction "1_1") (pintype "passive"))
      (node (ref "TP15") (pin "TP") (pinfunction "TP_TP") (pintype "input"))
      (node (ref "U2") (pin "8") (pinfunction "IO0_8") (pintype "bidirectional"))
      (node (ref "U3") (pin "3") (pinfunction "SQW/~{INT}_3") (pintype "output"))
    )
    (net (code "17") (name "IO{slash}BOOT") (class "Default")
      (node (ref "BOOT_BUTTON") (pin "4") (pinfunction "4_4") (pintype "passive"))
      (node (ref "C6") (pin "1") (pinfunction "1_1") (pintype "passive"))
      (node (ref "R_BOOT") (pin "1") (pinfunction "1_1") (pintype "passive"))
      (node (ref "U2") (pin "15") (pinfunction "IO9_15") (pintype "bidirectional"))
    )
    (net (code "18") (name "IO{slash}CHANGE") (class "Default")
      (node (ref "C10") (pin "1") (pinfunction "1_1") (pintype "passive"))
      (node (ref "CHANGE_BUTTON") (pin "4") (pinfunction "4_4") (pintype "passive"))
      (node (ref "R_CHANGE") (pin "1") (pinfunction "1_1") (pintype "passive"))
      (node (ref "U2") (pin "23") (pinfunction "IO15_23") (pintype "bidirectional"))
    )
    (net (code "19") (name "MISO") (class "Default")
      (node (ref "D12") (pin "2") (pinfunction "2_2") (pintype "passive"))
      (node (ref "J4") (pin "P7") (pinfunction "DAT0_P7") (pintype "bidirectional"))
      (node (ref "R8") (pin "1") (pinfunction "1_1") (pintype "passive"))
      (node (ref "TP6") (pin "TP") (pinfunction "TP_TP") (pintype "input"))
      (node (ref "U1") (pin "2") (pinfunction "DO(IO1)_2") (pintype "bidirectional"))
      (node (ref "U2") (pin "27") (pinfunction "IO2_27") (pintype "bidirectional"))
    )
    (net (code "20") (name "MOSI") (class "Default")
      (node (ref "D11") (pin "2") (pinfunction "2_2") (pintype "passive"))
      (node (ref "J1") (pin "14") (pinfunction "14_14") (pintype "bidirectional"))
      (node (ref "J4") (pin "P3") (pinfunction "CMD_P3") (pintype "bidirectional"))
      (node (ref "R7") (pin "1") (pinfunction "1_1") (pintype "passive"))
      (node (ref "TP7") (pin "TP") (pinfunction "TP_TP") (pintype "input"))
      (node (ref "U1") (pin "5") (pinfunction "DI(IO0)_5") (pintype "bidirectional"))
      (node (ref "U2") (pin "7") (pinfunction "IO7_7") (pintype "bidirectional"))
    )
    (net (code "21") (name "Net-(CHG_LED-PadC)") (class "Default")
      (node (ref "CHG_LED") (pin "C") (pinfunction "C_C") (pintype "passive"))
      (node (ref "R1_BAT") (pin "1") (pinfunction "1_1") (pintype "passive"))
    )
    (net (code "22") (name "Net-(D2-CATHODE)") (class "Default")
      (node (ref "C1_BAT1") (pin "1") (pinfunction "1_1") (pintype "passive"))
      (node (ref "D2") (pin "1") (pinfunction "CATHODE_1") (pintype "bidirectional"))
      (node (ref "IC4") (pin "1") (pinfunction "VIN_1") (pintype "bidirectional"))
      (node (ref "IC4") (pin "3") (pinfunction "CE_3") (pintype "bidirectional"))
      (node (ref "Q1") (pin "2") (pinfunction "S_2") (pintype "bidirectional"))
    )
    (net (code "23") (name "Net-(D3-A)") (class "Default")
      (node (ref "C4") (pin "1") (pinfunction "1_1") (pintype "passive"))
      (node (ref "D3") (pin "2") (pinfunction "A_2") (pintype "bidirectional"))
      (node (ref "D4") (pin "1") (pinfunction "K_1") (pintype "bidirectional"))
    )
    (net (code "24") (name "Net-(D7-CATHODE)") (class "Default")
      (node (ref "D7") (pin "1") (pinfunction "CATHODE_1") (pintype "bidirectional"))
      (node (ref "R_CAPACITOR") (pin "1") (pinfunction "1_1") (pintype "passive"))
    )
    (net (code "25") (name "Net-(EPD_C1-Pad2)") (class "Default")
      (node (ref "EPD_C1") (pin "2") (pinfunction "2_2") (pintype "passive"))
      (node (ref "J1") (pin "4") (pinfunction "4_4") (pintype "bidirectional"))
    )
    (net (code "26") (name "Net-(EPD_C2-Pad2)") (class "Default")
      (node (ref "EPD_C2") (pin "2") (pinfunction "2_2") (pintype "passive"))
      (node (ref "J1") (pin "5") (pinfunction "5_5") (pintype "bidirectional"))
    )
    (net (code "27") (name "Net-(EPD_C6-Pad2)") (class "Default")
      (node (ref "EPD_C6") (pin "2") (pinfunction "2_2") (pintype "passive"))
      (node (ref "J1") (pin "18") (pinfunction "18_18") (pintype "bidirectional"))
    )
    (net (code "28") (name "Net-(EPD_C7-Pad2)") (class "Default")
      (node (ref "EPD_C7") (pin "2") (pinfunction "2_2") (pintype "passive"))
      (node (ref "J1") (pin "19") (pinfunction "19_19") (pintype "bidirectional"))
    )
    (net (code "29") (name "Net-(EPD_C8-Pad2)") (class "Default")
      (node (ref "EPD_C8") (pin "2") (pinfunction "2_2") (pintype "passive"))
      (node (ref "J1") (pin "20") (pinfunction "20_20") (pintype "bidirectional"))
    )
    (net (code "30") (name "Net-(EPD_C10-Pad2)") (class "Default")
      (node (ref "EPD_C10") (pin "2") (pinfunction "2_2") (pintype "passive"))
      (node (ref "J1") (pin "22") (pinfunction "22_22") (pintype "bidirectional"))
    )
    (net (code "31") (name "Net-(EPD_C12-Pad2)") (class "Default")
      (node (ref "EPD_C12") (pin "2") (pinfunction "2_2") (pintype "passive"))
      (node (ref "J1") (pin "24") (pinfunction "24_24") (pintype "bidirectional"))
    )
    (net (code "32") (name "Net-(IC1-CT)") (class "Default")
      (node (ref "C_DELAY") (pin "1") (pinfunction "1_1") (pintype "passive"))
      (node (ref "IC1") (pin "5") (pinfunction "CT_5") (pintype "bidirectional"))
    )
    (net (code "33") (name "Net-(J2-PadA5)") (class "Default")
      (node (ref "J2") (pin "A5") (pinfunction "A5_A5") (pintype "bidirectional"))
      (node (ref "R2-USB1") (pin "2") (pinfunction "2_2") (pintype "passive"))
    )
    (net (code "34") (name "Net-(J2-PadB5)") (class "Default")
      (node (ref "J2") (pin "B5") (pinfunction "B5_B5") (pintype "bidirectional"))
      (node (ref "R2-USB") (pin "1") (pinfunction "1_1") (pintype "passive"))
    )
    (net (code "35") (name "Net-(MCP73831-PROG)") (class "Default")
      (node (ref "MCP73831") (pin "5") (pinfunction "PROG_5") (pintype "input"))
      (node (ref "R2_BAT") (pin "2") (pinfunction "2_2") (pintype "passive"))
    )
    (net (code "36") (name "Net-(MCP73831-STAT)") (class "Default")
      (node (ref "MCP73831") (pin "1") (pinfunction "STAT_1") (pintype "output"))
      (node (ref "R1_BAT") (pin "2") (pinfunction "2_2") (pintype "passive"))
    )
    (net (code "37") (name "PREVGH") (class "Default")
      (node (ref "D5") (pin "1") (pinfunction "K_1") (pintype "bidirectional"))
      (node (ref "EPD_C9") (pin "2") (pinfunction "2_2") (pintype "passive"))
      (node (ref "J1") (pin "21") (pinfunction "21_21") (pintype "bidirectional"))
    )
    (net (code "38") (name "PREVGL") (class "Default")
      (node (ref "D4") (pin "2") (pinfunction "A_2") (pintype "bidirectional"))
      (node (ref "EPD_C11") (pin "2") (pinfunction "2_2") (pintype "passive"))
      (node (ref "J1") (pin "23") (pinfunction "23_23") (pintype "bidirectional"))
    )
    (net (code "39") (name "RESE") (class "Default")
      (node (ref "J1") (pin "3") (pinfunction "3_3") (pintype "bidirectional"))
      (node (ref "Q3") (pin "2") (pinfunction "S_2") (pintype "bidirectional"))
      (node (ref "R3") (pin "2") (pinfunction "2_2") (pintype "passive"))
    )
    (net (code "40") (name "RESE'") (class "Default")
      (node (ref "R2") (pin "2") (pinfunction "2_2") (pintype "passive"))
      (node (ref "R3") (pin "1") (pinfunction "1_1") (pintype "passive"))
      (node (ref "SJ1") (pin "2") (pinfunction "2_2") (pintype "passive"))
    )
    (net (code "41") (name "RESET") (class "Default")
      (node (ref "C5") (pin "1") (pinfunction "1_1") (pintype "passive"))
      (node (ref "IC1") (pin "1") (pinfunction "VOUT_1") (pintype "bidirectional"))
      (node (ref "RESET_BUTTON") (pin "4") (pinfunction "4_4") (pintype "passive"))
      (node (ref "R_RESET") (pin "1") (pinfunction "1_1") (pintype "passive"))
      (node (ref "U2") (pin "3") (pinfunction "EN_3") (pintype "input"))
    )
    (net (code "42") (name "RTC_RST") (class "Default")
      (node (ref "U2") (pin "16") (pinfunction "IO18_16") (pintype "bidirectional"))
      (node (ref "U3") (pin "4") (pinfunction "~{RST}_4") (pintype "input"))
    )
    (net (code "43") (name "RX") (class "Default")
      (node (ref "TP2") (pin "TP") (pinfunction "TP_TP") (pintype "input"))
      (node (ref "U2") (pin "24") (pinfunction "RXD0/GPIO17_24") (pintype "bidirectional"))
    )
    (net (code "44") (name "SCK") (class "Default")
      (node (ref "D10") (pin "2") (pinfunction "2_2") (pintype "passive"))
      (node (ref "J1") (pin "13") (pinfunction "13_13") (pintype "bidirectional"))
      (node (ref "J4") (pin "P5") (pinfunction "CLK_P5") (pintype "bidirectional"))
      (node (ref "R6") (pin "1") (pinfunction "1_1") (pintype "passive"))
      (node (ref "TP8") (pin "TP") (pinfunction "TP_TP") (pintype "input"))
      (node (ref "U1") (pin "6") (pinfunction "CLK_6") (pintype "input"))
      (node (ref "U2") (pin "6") (pinfunction "IO6_6") (pintype "bidirectional"))
    )
    (net (code "45") (name "SCL") (class "Default")
      (node (ref "J3") (pin "4") (pinfunction "4_4") (pintype "passive"))
      (node (ref "R2-PINH") (pin "1") (pinfunction "1_1") (pintype "passive"))
      (node (ref "SENSOR2") (pin "4") (pinfunction "SCK_4") (pintype "input"))
      (node (ref "U2") (pin "20") (pinfunction "IO22_20") (pintype "bidirectional"))
      (node (ref "U3") (pin "16") (pinfunction "SCL_16") (pintype "input"))
      (node (ref "U4") (pin "7") (pinfunction "SCL_7") (pintype "input"))
    )
    (net (code "46") (name "SDA") (class "Default")
      (node (ref "J3") (pin "3") (pinfunction "3_3") (pintype "passive"))
      (node (ref "R1-PINH") (pin "1") (pinfunction "1_1") (pintype "passive"))
      (node (ref "SENSOR2") (pin "3") (pinfunction "SDI_3") (pintype "bidirectional"))
      (node (ref "U2") (pin "19") (pinfunction "IO21_19") (pintype "bidirectional"))
      (node (ref "U3") (pin "15") (pinfunction "SDA_15") (pintype "bidirectional"))
      (node (ref "U4") (pin "8") (pinfunction "SDA_8") (pintype "bidirectional"))
    )
    (net (code "47") (name "SRC") (class "Default")
      (node (ref "C4") (pin "2") (pinfunction "2_2") (pintype "passive"))
      (node (ref "D5") (pin "2") (pinfunction "A_2") (pintype "bidirectional"))
      (node (ref "L1") (pin "1") (pinfunction "1_1") (pintype "passive"))
      (node (ref "Q3") (pin "3") (pinfunction "D_3") (pintype "bidirectional"))
    )
    (net (code "48") (name "SS_SD") (class "Default")
      (node (ref "D8") (pin "2") (pinfunction "2_2") (pintype "passive"))
      (node (ref "J4") (pin "P2") (pinfunction "CD/DAT3_P2") (pintype "bidirectional"))
      (node (ref "R10") (pin "1") (pinfunction "1_1") (pintype "passive"))
      (node (ref "U2") (pin "4") (pinfunction "IO4_4") (pintype "bidirectional"))
    )
    (net (code "49") (name "TX") (class "Default")
      (node (ref "TP1") (pin "TP") (pinfunction "TP_TP") (pintype "input"))
      (node (ref "U2") (pin "25") (pinfunction "TXD0/GPIO16_25") (pintype "bidirectional"))
    )
    (net (code "50") (name "USB_D+") (class "Default")
      (node (ref "D1") (pin "4") (pinfunction "I/O2_2_4") (pintype "bidirectional"))
      (node (ref "U2") (pin "14") (pinfunction "IO13_14") (pintype "bidirectional"))
    )
    (net (code "51") (name "USB_D-") (class "Default")
      (node (ref "D1") (pin "6") (pinfunction "I/O1_2_6") (pintype "bidirectional"))
      (node (ref "U2") (pin "13") (pinfunction "IO12_13") (pintype "bidirectional"))
    )
    (net (code "52") (name "VBAT") (class "Default")
      (node (ref "C2_BAT") (pin "1") (pinfunction "1_1") (pintype "passive"))
      (node (ref "MCP73831") (pin "3") (pinfunction "VBAT_3") (pintype "power_in"))
      (node (ref "Q1") (pin "3") (pinfunction "D_3") (pintype "bidirectional"))
      (node (ref "TP3") (pin "TP") (pinfunction "TP_TP") (pintype "input"))
      (node (ref "U4") (pin "2") (pinfunction "CELL_2") (pintype "power_in"))
      (node (ref "U4") (pin "3") (pinfunction "VDD_3") (pintype "power_in"))
    )
    (net (code "53") (name "VBUS") (class "Default")
      (node (ref "C1_BAT") (pin "1") (pinfunction "1_1") (pintype "passive"))
      (node (ref "C4_USB") (pin "1") (pinfunction "1_1") (pintype "passive"))
      (node (ref "C5_USB") (pin "1") (pinfunction "1_1") (pintype "passive"))
      (node (ref "CHG_LED") (pin "A") (pinfunction "A_A") (pintype "passive"))
      (node (ref "D1") (pin "2") (pinfunction "GND_2") (pintype "bidirectional"))
      (node (ref "D2") (pin "2") (pinfunction "ANODE_2") (pintype "bidirectional"))
      (node (ref "MCP73831") (pin "4") (pinfunction "VIN_4") (pintype "power_in"))
      (node (ref "PFMF.050.1") (pin "2") (pinfunction "2_2") (pintype "passive"))
      (node (ref "R1_PWRUSB") (pin "2") (pinfunction "2_2") (pintype "passive"))
      (node (ref "TP14") (pin "TP") (pinfunction "TP_TP") (pintype "input"))
    )
    (net (code "54") (name "VRTC") (class "Default")
      (node (ref "C10_SUPERCAP") (pin "1") (pinfunction "1_1") (pintype "passive"))
      (node (ref "C8") (pin "1") (pinfunction "1_1") (pintype "passive"))
      (node (ref "R_CAPACITOR") (pin "2") (pinfunction "2_2") (pintype "passive"))
      (node (ref "U3") (pin "14") (pinfunction "VBAT_14") (pintype "power_in"))
    )
    (net (code "55") (name "VUSB") (class "Default")
      (node (ref "J2") (pin "A4") (pinfunction "A4_A4") (pintype "bidirectional"))
      (node (ref "J2") (pin "A9") (pinfunction "A9_A9") (pintype "bidirectional"))
      (node (ref "J2") (pin "B4") (pinfunction "B4_B4") (pintype "bidirectional"))
      (node (ref "J2") (pin "B9") (pinfunction "B9_B9") (pintype "bidirectional"))
      (node (ref "PFMF.050.1") (pin "1") (pinfunction "1_1") (pintype "passive"))
    )
    (net (code "56") (name "unconnected-(BOOT_BUTTON-Pad1)") (class "Default")
      (node (ref "BOOT_BUTTON") (pin "1") (pinfunction "1_1") (pintype "passive"))
    )
    (net (code "57") (name "unconnected-(BOOT_BUTTON-Pad3)") (class "Default")
      (node (ref "BOOT_BUTTON") (pin "3") (pinfunction "3_3") (pintype "passive"))
    )
    (net (code "58") (name "unconnected-(CHANGE_BUTTON-Pad1)") (class "Default")
      (node (ref "CHANGE_BUTTON") (pin "1") (pinfunction "1_1") (pintype "passive"))
    )
    (net (code "59") (name "unconnected-(CHANGE_BUTTON-Pad3)") (class "Default")
      (node (ref "CHANGE_BUTTON") (pin "3") (pinfunction "3_3") (pintype "passive"))
    )
    (net (code "60") (name "unconnected-(IC1-NC-Pad4)") (class "Default")
      (node (ref "IC1") (pin "4") (pinfunction "NC_4") (pintype "no_connect"))
    )
    (net (code "61") (name "unconnected-(IC4-NC-Pad4)") (class "Default")
      (node (ref "IC4") (pin "4") (pinfunction "NC_4") (pintype "no_connect"))
    )
    (net (code "62") (name "unconnected-(J1-Pad1)") (class "Default")
      (node (ref "J1") (pin "1") (pinfunction "1_1") (pintype "bidirectional"))
    )
    (net (code "63") (name "unconnected-(J1-Pad6)") (class "Default")
      (node (ref "J1") (pin "6") (pinfunction "6_6") (pintype "bidirectional"))
    )
    (net (code "64") (name "unconnected-(J1-Pad7)") (class "Default")
      (node (ref "J1") (pin "7") (pinfunction "7_7") (pintype "bidirectional"))
    )
    (net (code "65") (name "unconnected-(J2-PadA8)") (class "Default")
      (node (ref "J2") (pin "A8") (pinfunction "A8_A8") (pintype "bidirectional"))
    )
    (net (code "66") (name "unconnected-(J2-PadB8)") (class "Default")
      (node (ref "J2") (pin "B8") (pinfunction "B8_B8") (pintype "bidirectional"))
    )
    (net (code "67") (name "unconnected-(J4-DAT1-PadP8)") (class "Default")
      (node (ref "J4") (pin "P8") (pinfunction "DAT1_P8") (pintype "bidirectional"))
    )
    (net (code "68") (name "unconnected-(J4-DAT2-PadP1)") (class "Default")
      (node (ref "J4") (pin "P1") (pinfunction "DAT2_P1") (pintype "bidirectional"))
    )
    (net (code "69") (name "unconnected-(J4-DETECTION_1-PadS1)") (class "Default")
      (node (ref "J4") (pin "S1") (pinfunction "DETECTION_1_S1") (pintype "bidirectional"))
    )
    (net (code "70") (name "unconnected-(J4-DETECTION_2-PadS2)") (class "Default")
      (node (ref "J4") (pin "S2") (pinfunction "DETECTION_2_S2") (pintype "bidirectional"))
    )
    (net (code "71") (name "unconnected-(Q1-G-Pad1)") (class "Default")
      (node (ref "Q1") (pin "1") (pinfunction "G_1") (pintype "bidirectional"))
    )
    (net (code "72") (name "unconnected-(RESET_BUTTON-Pad1)") (class "Default")
      (node (ref "RESET_BUTTON") (pin "1") (pinfunction "1_1") (pintype "passive"))
    )
    (net (code "73") (name "unconnected-(RESET_BUTTON-Pad3)") (class "Default")
      (node (ref "RESET_BUTTON") (pin "3") (pinfunction "3_3") (pintype "passive"))
    )
    (net (code "74") (name "unconnected-(U2-NC-Pad22)") (class "Default")
      (node (ref "U2") (pin "22") (pinfunction "NC_22") (pintype "no_connect"))
    )
    (net (code "75") (name "unconnected-(U4-~{ALERT}-Pad5)") (class "Default")
      (node (ref "U4") (pin "5") (pinfunction "~{ALERT}_5") (pintype "output"))
    )
  )
)
